# badge_schematic.net
KiCad netlist of a schematic drawn in EAGLE
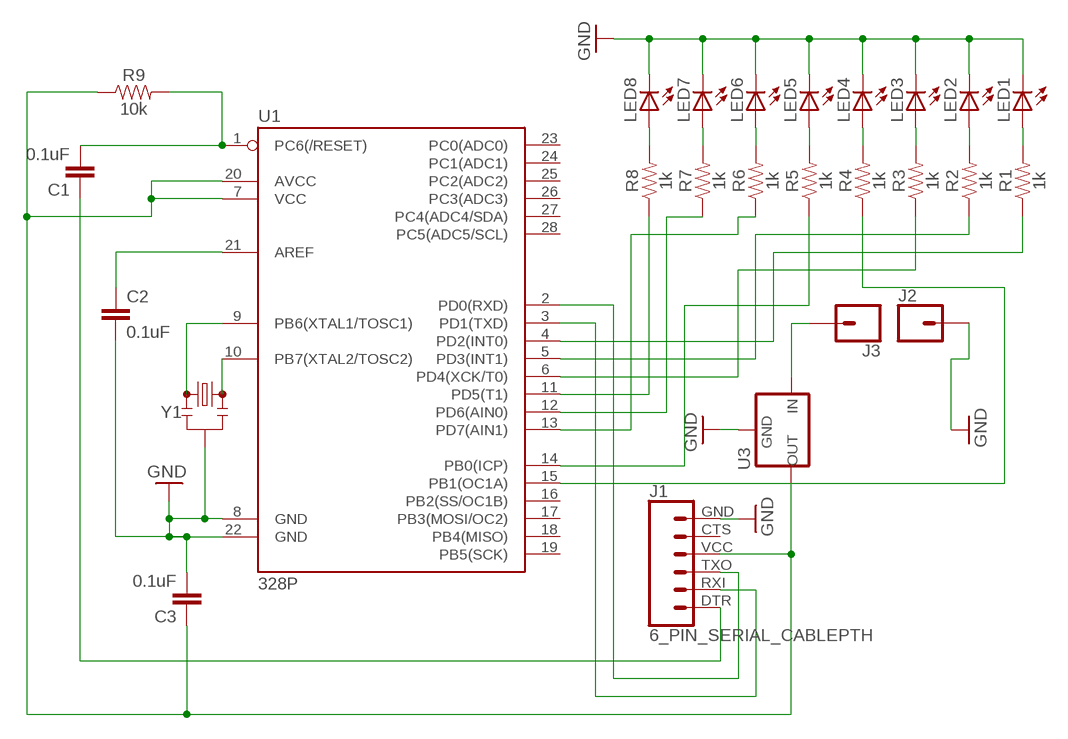
[diagram p0: schematic, sheet 1]

(export (version "E")
  (design (tool "Eeschema 10.0.6"))
  (components
    (comp (ref "C1")
      (value "0.1uF")
      (footprint "eagle-import:CAP-PTH-SMALL-KIT")
      (libsource (lib "eagle-import") (part "0.1UF-KIT-EZ-50V-20%"))
    )
    (comp (ref "C2")
      (value "0.1uF")
      (footprint "eagle-import:CAP-PTH-SMALL-KIT")
      (libsource (lib "eagle-import") (part "0.1UF-KIT-EZ-50V-20%"))
    )
    (comp (ref "C3")
      (value "0.1uF")
      (footprint "eagle-import:CAP-PTH-SMALL-KIT")
      (libsource (lib "eagle-import") (part "0.1UF-KIT-EZ-50V-20%"))
    )
    (comp (ref "J1")
      (value "6_PIN_SERIAL_CABLEPTH")
      (footprint "eagle-import:FTDI_BASIC")
      (libsource (lib "eagle-import") (part "6_PIN_SERIAL_CABLEPTH"))
    )
    (comp (ref "J2")
      (value "CONN_01")
      (footprint "eagle-import:1X01")
      (libsource (lib "eagle-import") (part "CONN_01"))
    )
    (comp (ref "J3")
      (value "CONN_01")
      (footprint "eagle-import:1X01")
      (libsource (lib "eagle-import") (part "CONN_01"))
    )
    (comp (ref "LED1")
      (value "LED5MM")
      (footprint "eagle-import:LED5MM")
      (libsource (lib "eagle-import") (part "LED5MM"))
    )
    (comp (ref "LED2")
      (value "LED5MM")
      (footprint "eagle-import:LED5MM")
      (libsource (lib "eagle-import") (part "LED5MM"))
    )
    (comp (ref "LED3")
      (value "LED5MM")
      (footprint "eagle-import:LED5MM")
      (libsource (lib "eagle-import") (part "LED5MM"))
    )
    (comp (ref "LED4")
      (value "LED5MM")
      (footprint "eagle-import:LED5MM")
      (libsource (lib "eagle-import") (part "LED5MM"))
    )
    (comp (ref "LED5")
      (value "LED5MM")
      (footprint "eagle-import:LED5MM")
      (libsource (lib "eagle-import") (part "LED5MM"))
    )
    (comp (ref "LED6")
      (value "LED5MM")
      (footprint "eagle-import:LED5MM")
      (libsource (lib "eagle-import") (part "LED5MM"))
    )
    (comp (ref "LED7")
      (value "LED5MM")
      (footprint "eagle-import:LED5MM")
      (libsource (lib "eagle-import") (part "LED5MM"))
    )
    (comp (ref "LED8")
      (value "LED5MM")
      (footprint "eagle-import:LED5MM")
      (libsource (lib "eagle-import") (part "LED5MM"))
    )
    (comp (ref "R1")
      (value "1k")
      (footprint "eagle-import:AXIAL-0.3")
      (libsource (lib "eagle-import") (part "1KOHM-HORIZ-1/4W-1%"))
    )
    (comp (ref "R2")
      (value "1k")
      (footprint "eagle-import:AXIAL-0.3")
      (libsource (lib "eagle-import") (part "1KOHM-HORIZ-1/4W-1%"))
    )
    (comp (ref "R3")
      (value "1k")
      (footprint "eagle-import:AXIAL-0.3")
      (libsource (lib "eagle-import") (part "1KOHM-HORIZ-1/4W-1%"))
    )
    (comp (ref "R4")
      (value "1k")
      (footprint "eagle-import:AXIAL-0.3")
      (libsource (lib "eagle-import") (part "1KOHM-HORIZ-1/4W-1%"))
    )
    (comp (ref "R5")
      (value "1k")
      (footprint "eagle-import:AXIAL-0.3")
      (libsource (lib "eagle-import") (part "1KOHM-HORIZ-1/4W-1%"))
    )
    (comp (ref "R6")
      (value "1k")
      (footprint "eagle-import:AXIAL-0.3")
      (libsource (lib "eagle-import") (part "1KOHM-HORIZ-1/4W-1%"))
    )
    (comp (ref "R7")
      (value "1k")
      (footprint "eagle-import:AXIAL-0.3")
      (libsource (lib "eagle-import") (part "1KOHM-HORIZ-1/4W-1%"))
    )
    (comp (ref "R8")
      (value "1k")
      (footprint "eagle-import:AXIAL-0.3")
      (libsource (lib "eagle-import") (part "1KOHM-HORIZ-1/4W-1%"))
    )
    (comp (ref "R9")
      (value "10k")
      (footprint "eagle-import:AXIAL-0.3")
      (libsource (lib "eagle-import") (part "10KOHM-HORIZ-1/4W-1%"))
    )
    (comp (ref "U1")
      (value "328P")
      (footprint "eagle-import:DIP28")
      (libsource (lib "eagle-import") (part "ATMEGA328P_PDIP"))
    )
    (comp (ref "U3")
      (value "V_REG_78XXTO-92_UNTESTED")
      (footprint "eagle-import:TO-92")
      (libsource (lib "eagle-import") (part "V_REG_78XXTO-92_UNTESTED"))
    )
    (comp (ref "Y1")
      (value "RESONATORPTH-7.6X3.8")
      (footprint "eagle-import:RESONATOR-PTH-7.6X3.8")
      (libsource (lib "eagle-import") (part "RESONATORPTH-7.6X3.8"))
    )
  )
  (nets
    (net (code "1") (name "GND") (class "Default")
      (node (ref "C2") (pin "2") (pinfunction "2_2") (pintype "passive"))
      (node (ref "C3") (pin "2") (pinfunction "2_2") (pintype "passive"))
      (node (ref "J1") (pin "GND") (pinfunction "6_GND") (pintype "passive"))
      (node (ref "J2") (pin "1") (pinfunction "1_1") (pintype "passive"))
      (node (ref "LED1") (pin "K") (pinfunction "C_K") (pintype "passive"))
      (node (ref "LED2") (pin "K") (pinfunction "C_K") (pintype "passive"))
      (node (ref "LED3") (pin "K") (pinfunction "C_K") (pintype "passive"))
      (node (ref "LED4") (pin "K") (pinfunction "C_K") (pintype "passive"))
      (node (ref "LED5") (pin "K") (pinfunction "C_K") (pintype "passive"))
      (node (ref "LED6") (pin "K") (pinfunction "C_K") (pintype "passive"))
      (node (ref "LED7") (pin "K") (pinfunction "C_K") (pintype "passive"))
      (node (ref "LED8") (pin "K") (pinfunction "C_K") (pintype "passive"))
      (node (ref "U1") (pin "22") (pinfunction "GND_22") (pintype "bidirectional"))
      (node (ref "U1") (pin "8") (pinfunction "GND_8") (pintype "bidirectional"))
      (node (ref "U3") (pin "2") (pinfunction "GND_2") (pintype "input"))
      (node (ref "Y1") (pin "2") (pinfunction "2_2") (pintype "passive"))
    )
    (net (code "2") (name "Net-(J1-1)") (class "Default")
      (node (ref "C1") (pin "1") (pinfunction "1_1") (pintype "passive"))
      (node (ref "J1") (pin "DTR") (pinfunction "1_DTR") (pintype "passive"))
    )
    (net (code "3") (name "Net-(J1-2)") (class "Default")
      (node (ref "J1") (pin "RXI") (pinfunction "2_RXI") (pintype "passive"))
      (node (ref "U1") (pin "3") (pinfunction "PD1(TXD)_3") (pintype "bidirectional"))
    )
    (net (code "4") (name "Net-(J1-3)") (class "Default")
      (node (ref "J1") (pin "TXO") (pinfunction "3_TXO") (pintype "passive"))
      (node (ref "U1") (pin "2") (pinfunction "PD0(RXD)_2") (pintype "bidirectional"))
    )
    (net (code "5") (name "Net-(J1-4)") (class "Default")
      (node (ref "C3") (pin "1") (pinfunction "1_1") (pintype "passive"))
      (node (ref "J1") (pin "VCC") (pinfunction "4_VCC") (pintype "passive"))
      (node (ref "R9") (pin "P$1") (pinfunction "1_P$1") (pintype "passive"))
      (node (ref "U1") (pin "20") (pinfunction "AVCC_20") (pintype "bidirectional"))
      (node (ref "U1") (pin "7") (pinfunction "VCC_7") (pintype "bidirectional"))
      (node (ref "U3") (pin "1") (pinfunction "OUT_1") (pintype "passive"))
    )
    (net (code "6") (name "Net-(R1-1)") (class "Default")
      (node (ref "R1") (pin "P$1") (pinfunction "1_P$1") (pintype "passive"))
      (node (ref "U1") (pin "4") (pinfunction "PD2(INT0)_4") (pintype "bidirectional"))
    )
    (net (code "7") (name "Net-(R1-2)") (class "Default")
      (node (ref "LED1") (pin "A") (pinfunction "A_A") (pintype "passive"))
      (node (ref "R1") (pin "P$2") (pinfunction "2_P$2") (pintype "passive"))
    )
    (net (code "8") (name "Net-(R2-1)") (class "Default")
      (node (ref "R2") (pin "P$1") (pinfunction "1_P$1") (pintype "passive"))
      (node (ref "U1") (pin "5") (pinfunction "PD3(INT1)_5") (pintype "bidirectional"))
    )
    (net (code "9") (name "Net-(R2-2)") (class "Default")
      (node (ref "LED2") (pin "A") (pinfunction "A_A") (pintype "passive"))
      (node (ref "R2") (pin "P$2") (pinfunction "2_P$2") (pintype "passive"))
    )
    (net (code "10") (name "Net-(R3-1)") (class "Default")
      (node (ref "R3") (pin "P$1") (pinfunction "1_P$1") (pintype "passive"))
      (node (ref "U1") (pin "6") (pinfunction "PD4(XCK/T0)_6") (pintype "bidirectional"))
    )
    (net (code "11") (name "Net-(R3-2)") (class "Default")
      (node (ref "LED3") (pin "A") (pinfunction "A_A") (pintype "passive"))
      (node (ref "R3") (pin "P$2") (pinfunction "2_P$2") (pintype "passive"))
    )
    (net (code "12") (name "Net-(R4-1)") (class "Default")
      (node (ref "R4") (pin "P$1") (pinfunction "1_P$1") (pintype "passive"))
      (node (ref "U1") (pin "15") (pinfunction "PB1(OC1A)_15") (pintype "bidirectional"))
    )
    (net (code "13") (name "Net-(R4-2)") (class "Default")
      (node (ref "LED4") (pin "A") (pinfunction "A_A") (pintype "passive"))
      (node (ref "R4") (pin "P$2") (pinfunction "2_P$2") (pintype "passive"))
    )
    (net (code "14") (name "Net-(R5-1)") (class "Default")
      (node (ref "R5") (pin "P$1") (pinfunction "1_P$1") (pintype "passive"))
      (node (ref "U1") (pin "14") (pinfunction "PB0(ICP)_14") (pintype "bidirectional"))
    )
    (net (code "15") (name "Net-(R5-2)") (class "Default")
      (node (ref "LED5") (pin "A") (pinfunction "A_A") (pintype "passive"))
      (node (ref "R5") (pin "P$2") (pinfunction "2_P$2") (pintype "passive"))
    )
    (net (code "16") (name "Net-(R6-1)") (class "Default")
      (node (ref "R6") (pin "P$1") (pinfunction "1_P$1") (pintype "passive"))
      (node (ref "U1") (pin "13") (pinfunction "PD7(AIN1)_13") (pintype "bidirectional"))
    )
    (net (code "17") (name "Net-(R6-2)") (class "Default")
      (node (ref "LED6") (pin "A") (pinfunction "A_A") (pintype "passive"))
      (node (ref "R6") (pin "P$2") (pinfunction "2_P$2") (pintype "passive"))
    )
    (net (code "18") (name "Net-(R7-1)") (class "Default")
      (node (ref "R7") (pin "P$1") (pinfunction "1_P$1") (pintype "passive"))
      (node (ref "U1") (pin "12") (pinfunction "PD6(AIN0)_12") (pintype "bidirectional"))
    )
    (net (code "19") (name "Net-(R7-2)") (class "Default")
      (node (ref "LED7") (pin "A") (pinfunction "A_A") (pintype "passive"))
      (node (ref "R7") (pin "P$2") (pinfunction "2_P$2") (pintype "passive"))
    )
    (net (code "20") (name "Net-(R8-1)") (class "Default")
      (node (ref "R8") (pin "P$1") (pinfunction "1_P$1") (pintype "passive"))
      (node (ref "U1") (pin "11") (pinfunction "PD5(T1)_11") (pintype "bidirectional"))
    )
    (net (code "21") (name "Net-(R8-2)") (class "Default")
      (node (ref "LED8") (pin "A") (pinfunction "A_A") (pintype "passive"))
      (node (ref "R8") (pin "P$2") (pinfunction "2_P$2") (pintype "passive"))
    )
    (net (code "22") (name "Net-(R9-2)") (class "Default")
      (node (ref "C1") (pin "2") (pinfunction "2_2") (pintype "passive"))
      (node (ref "R9") (pin "P$2") (pinfunction "2_P$2") (pintype "passive"))
      (node (ref "U1") (pin "1") (pinfunction "PC6(/RESET)_1") (pintype "bidirectional"))
    )
    (net (code "23") (name "Net-(U1-AREF)") (class "Default")
      (node (ref "C2") (pin "1") (pinfunction "1_1") (pintype "passive"))
      (node (ref "U1") (pin "21") (pinfunction "AREF_21") (pintype "bidirectional"))
    )
    (net (code "24") (name "Net-(U1-PB6(XTAL1{slash}TOSC1))") (class "Default")
      (node (ref "U1") (pin "9") (pinfunction "PB6(XTAL1/TOSC1)_9") (pintype "bidirectional"))
      (node (ref "Y1") (pin "1") (pinfunction "1_1") (pintype "passive"))
    )
    (net (code "25") (name "Net-(U1-PB7(XTAL2{slash}TOSC2))") (class "Default")
      (node (ref "U1") (pin "10") (pinfunction "PB7(XTAL2/TOSC2)_10") (pintype "bidirectional"))
      (node (ref "Y1") (pin "3") (pinfunction "3_3") (pintype "passive"))
    )
    (net (code "26") (name "Net-(U3-IN)") (class "Default")
      (node (ref "J3") (pin "1") (pinfunction "1_1") (pintype "passive"))
      (node (ref "U3") (pin "3") (pinfunction "IN_3") (pintype "input"))
    )
    (net (code "27") (name "unconnected-(J1-5-PadCTS)") (class "Default")
      (node (ref "J1") (pin "CTS") (pinfunction "5_CTS") (pintype "passive"))
    )
    (net (code "28") (name "unconnected-(U1-PB2(SS{slash}OC1B)-Pad16)") (class "Default")
      (node (ref "U1") (pin "16") (pinfunction "PB2(SS/OC1B)_16") (pintype "bidirectional"))
    )
    (net (code "29") (name "unconnected-(U1-PB3(MOSI{slash}OC2)-Pad17)") (class "Default")
      (node (ref "U1") (pin "17") (pinfunction "PB3(MOSI/OC2)_17") (pintype "bidirectional"))
    )
    (net (code "30") (name "unconnected-(U1-PB4(MISO)-Pad18)") (class "Default")
      (node (ref "U1") (pin "18") (pinfunction "PB4(MISO)_18") (pintype "bidirectional"))
    )
    (net (code "31") (name "unconnected-(U1-PB5(SCK)-Pad19)") (class "Default")
      (node (ref "U1") (pin "19") (pinfunction "PB5(SCK)_19") (pintype "bidirectional"))
    )
    (net (code "32") (name "unconnected-(U1-PC0(ADC0)-Pad23)") (class "Default")
      (node (ref "U1") (pin "23") (pinfunction "PC0(ADC0)_23") (pintype "bidirectional"))
    )
    (net (code "33") (name "unconnected-(U1-PC1(ADC1)-Pad24)") (class "Default")
      (node (ref "U1") (pin "24") (pinfunction "PC1(ADC1)_24") (pintype "bidirectional"))
    )
    (net (code "34") (name "unconnected-(U1-PC2(ADC2)-Pad25)") (class "Default")
      (node (ref "U1") (pin "25") (pinfunction "PC2(ADC2)_25") (pintype "bidirectional"))
    )
    (net (code "35") (name "unconnected-(U1-PC3(ADC3)-Pad26)") (class "Default")
      (node (ref "U1") (pin "26") (pinfunction "PC3(ADC3)_26") (pintype "bidirectional"))
    )
    (net (code "36") (name "unconnected-(U1-PC4(ADC4{slash}SDA)-Pad27)") (class "Default")
      (node (ref "U1") (pin "27") (pinfunction "PC4(ADC4/SDA)_27") (pintype "bidirectional"))
    )
    (net (code "37") (name "unconnected-(U1-PC5(ADC5{slash}SCL)-Pad28)") (class "Default")
      (node (ref "U1") (pin "28") (pinfunction "PC5(ADC5/SCL)_28") (pintype "bidirectional"))
    )
  )
)
